# Sheet1.net
KiCad netlist of a schematic drawn in Altium Designer
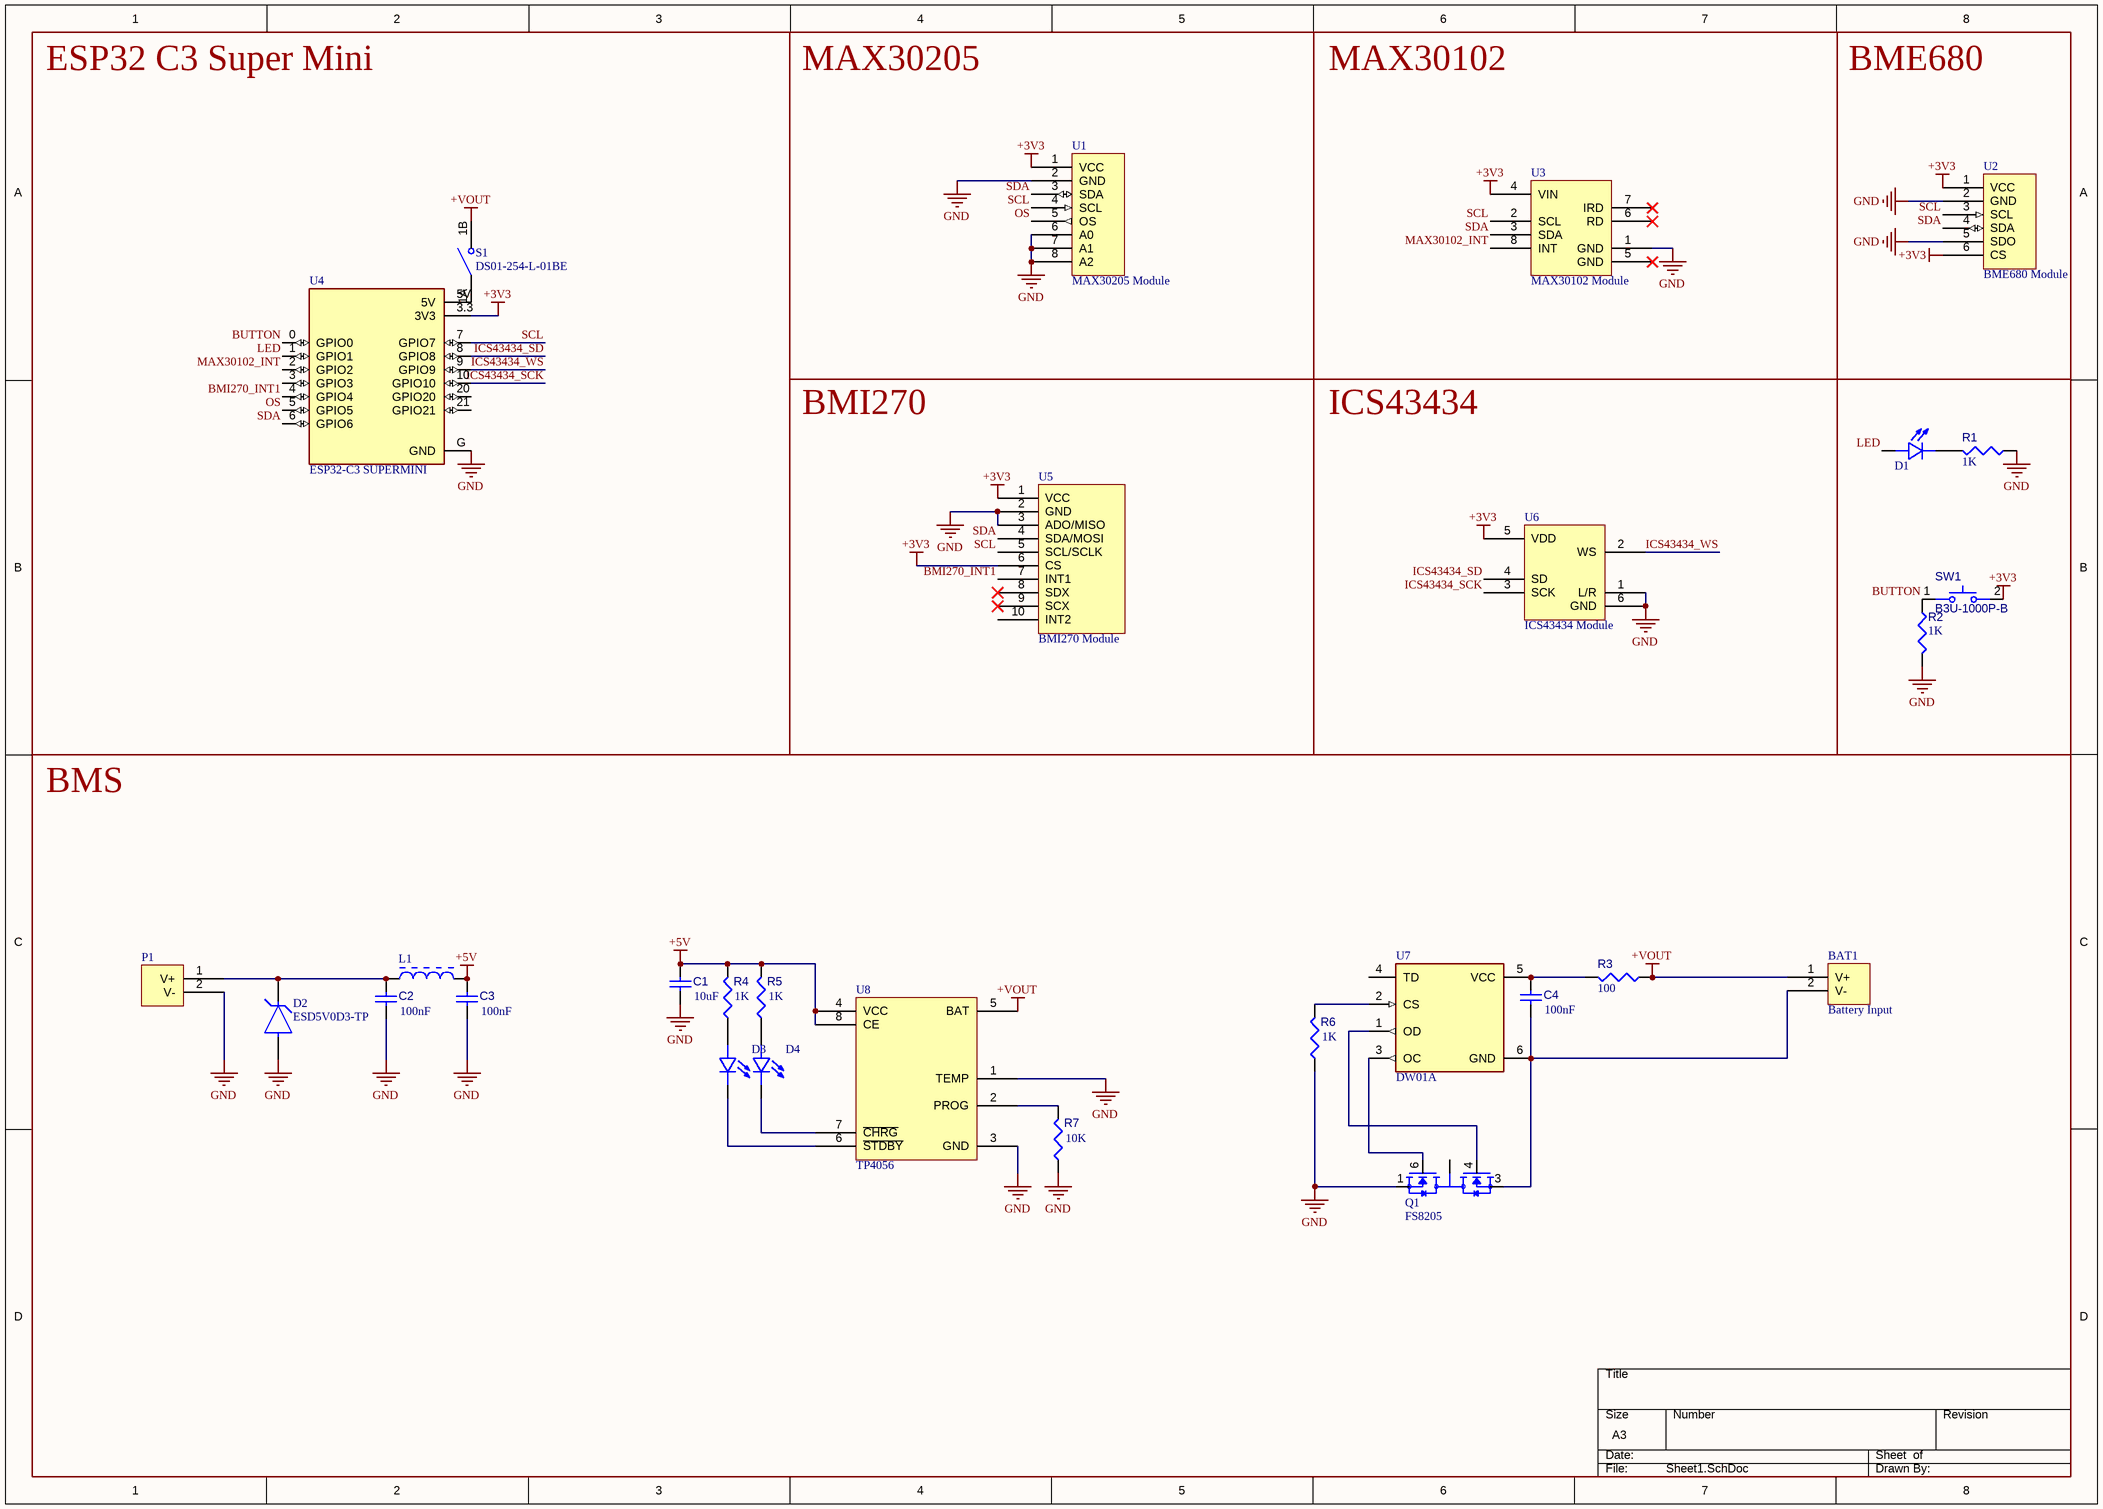
[diagram p0: Sheet1.SchDoc]

(export (version "E")
  (design (tool "Eeschema 10.0.6"))
  (components
    (comp (ref "BAT1")
      (value "Battery Input")
      (footprint "Battery Input-Footprint-1")
      (libsource (lib "personal workspace") (part "Battery Input-Symbol-1"))
    )
    (comp (ref "C1")
      (value "10uF")
      (footprint "Capacitor 0603-Footprint-1")
      (description "Capacitor 0603")
      (libsource (lib "personal workspace") (part "CAP-NP-2"))
    )
    (comp (ref "C2")
      (value "100nF")
      (footprint "Capacitor 0603-Footprint-1")
      (description "Capacitor 0603")
      (libsource (lib "personal workspace") (part "CAP-NP-2"))
    )
    (comp (ref "C3")
      (value "100nF")
      (footprint "Capacitor 0603-Footprint-1")
      (description "Capacitor 0603")
      (libsource (lib "personal workspace") (part "CAP-NP-2"))
    )
    (comp (ref "C4")
      (value "100nF")
      (footprint "Capacitor 0603-Footprint-1")
      (description "Capacitor 0603")
      (libsource (lib "personal workspace") (part "CAP-NP-2"))
    )
    (comp (ref "D1")
      (value "LED 0805")
      (footprint "LEDC2012X120N")
      (description "LED;Red;11mcd;0.061In.Dia.;SMD;100mA;2V Vf;635nm;140deg;SMD;White Diffused;5V Vr")
      (fields
        (field (name "MF") "Lumex Opto/Components")
        (field (name "MP") "SML-LXT0805IW-TR")
        (field (name "SOURCE") "SML-LXT0805IW-TR.SchLib")
      )
      (libsource (lib "") (part "SML-LXT0805IW-TR_1"))
    )
    (comp (ref "D2")
      (value "ESD5V0D3-TP")
      (footprint "FP-SOD-323-IPC_B")
      (description "TVS DIODE 5V 15.5V SOD323")
      (libsource (lib "Altium Content Vault") (part "f813f71cba58e380607f5dd3caf9714"))
    )
    (comp (ref "D3")
      (value "LED 0805")
      (footprint "LEDC2012X120N")
      (description "LED;Red;11mcd;0.061In.Dia.;SMD;100mA;2V Vf;635nm;140deg;SMD;White Diffused;5V Vr")
      (fields
        (field (name "MF") "Lumex Opto/Components")
        (field (name "MP") "SML-LXT0805IW-TR")
        (field (name "SOURCE") "SML-LXT0805IW-TR.SchLib")
      )
      (libsource (lib "personal workspace") (part "SML-LXT0805IW-TR"))
    )
    (comp (ref "D4")
      (value "LED 0805")
      (footprint "LEDC2012X120N")
      (description "LED;Red;11mcd;0.061In.Dia.;SMD;100mA;2V Vf;635nm;140deg;SMD;White Diffused;5V Vr")
      (fields
        (field (name "MF") "Lumex Opto/Components")
        (field (name "MP") "SML-LXT0805IW-TR")
        (field (name "SOURCE") "SML-LXT0805IW-TR.SchLib")
      )
      (libsource (lib "personal workspace") (part "SML-LXT0805IW-TR"))
    )
    (comp (ref "L1")
      (value "Ferrite Bead")
      (footprint "INDC2013X105X50ML20T20")
      (fields (field (name "TOLERANCE") "25%") (field (name "MANUFACTURER") "Murata"))
      (libsource (lib "personal workspace") (part "IND-FB-2"))
    )
    (comp (ref "P1")
      (value "Magnetic Connector 2-Pin 2.54mm")
      (footprint "Magnetic Connector 2-Pin 2.54mm-Footprint-1")
      (libsource (lib "personal workspace") (part "Magnetic Connector 2-Pin 2.54mm-Symbol-1"))
    )
    (comp (ref "Q1")
      (value "FS8205")
      (footprint "SOT95P280X145-6N")
      (description "20V 9A 1.5W Surface Mount SOT-23-6")
      (fields (field (name "MF") "Fortune Semiconductor"))
      (libsource (lib "personal workspace") (part "FS8205"))
    )
    (comp (ref "R1")
      (value "1K")
      (footprint "RESC1608X55X25NL10T15")
      (description "Resistor 0603")
      (libsource (lib "personal workspace") (part "RES-2"))
    )
    (comp (ref "R2")
      (value "1K")
      (footprint "RESC1608X55X25NL10T15")
      (description "Resistor 0603")
      (libsource (lib "personal workspace") (part "RES-2"))
    )
    (comp (ref "R3")
      (value "100")
      (footprint "RESC1608X55X25NL10T15")
      (description "Resistor 0603")
      (libsource (lib "personal workspace") (part "RES-2"))
    )
    (comp (ref "R4")
      (value "1K")
      (footprint "RESC1608X55X25NL10T15")
      (description "Resistor 0603")
      (libsource (lib "personal workspace") (part "RES-2"))
    )
    (comp (ref "R5")
      (value "1K")
      (footprint "RESC1608X55X25NL10T15")
      (description "Resistor 0603")
      (libsource (lib "personal workspace") (part "RES-2"))
    )
    (comp (ref "R6")
      (value "1K")
      (footprint "RESC1608X55X25NL10T15")
      (description "Resistor 0603")
      (libsource (lib "personal workspace") (part "RES-2"))
    )
    (comp (ref "R7")
      (value "10K")
      (footprint "RESC1608X55X25NL10T15")
      (description "Resistor 0603")
      (libsource (lib "personal workspace") (part "RES-2"))
    )
    (comp (ref "S1")
      (value "DS01-254-L-01BE")
      (footprint "SW_DS01-254-L-01BE")
      (description "1 Position, Through Hole, 2.54 mm Pitch, Raised Slide Actuator, Flat Bottom, Long Pin, DIP Switch")
      (fields (field (name "MF") "Same Sky"))
      (libsource (lib "personal workspace") (part "DS01-254-L-01BE"))
    )
    (comp (ref "SW1")
      (value "B3U-1000P-B")
      (footprint "OMRON-B3U-1000P-2-B_V")
      (libsource (lib "personal workspace") (part "CMP-00164-6"))
    )
    (comp (ref "U1")
      (value "MAX30205 Module")
      (footprint "MAX30205 Module-Footprint-1")
      (libsource (lib "personal workspace") (part "MAX30205 Module-Symbol-1"))
    )
    (comp (ref "U2")
      (value "BME680 Module")
      (footprint "BME680 Module-Footprint-1")
      (libsource (lib "personal workspace") (part "BME680 Module-Symbol-1"))
    )
    (comp (ref "U3")
      (value "MAX30102 Module")
      (footprint "MAX30102 Module-Footprint-1")
      (libsource (lib "personal workspace") (part "MAX30102 Module-Symbol-1"))
    )
    (comp (ref "U4")
      (value "ESP32-C3 SUPERMINI")
      (footprint "MODULE_ESP32-C3_SUPERMINI_TH")
      (fields (field (name "MF") "Espressif Systems") (field (name "MP") "ESP32-C3 SuperMini_TH"))
      (libsource (lib "personal workspace") (part "ESP32-C3_SUPERMINI_TH"))
    )
    (comp (ref "U5")
      (value "BMI270 Module")
      (footprint "BMI270 Module-Footprint-1")
      (libsource (lib "personal workspace") (part "BMI270 Module-Symbol-1"))
    )
    (comp (ref "U6")
      (value "ICS43434 Module")
      (footprint "ICS43434 Module-Footprint-1")
      (libsource (lib "personal workspace") (part "ICS43434 Module-Symbol-1"))
    )
    (comp (ref "U7")
      (value "DW01A")
      (footprint "SOT95P280X145-6N")
      (description "One Cell Lithium-ion/Polymer Battery Protection IC")
      (fields (field (name "MF") "Fortune Semiconductor"))
      (libsource (lib "personal workspace") (part "DW01A"))
    )
    (comp (ref "U8")
      (value "TP4056")
      (footprint "SOP127P600X200-8N")
      (description "IC Socket, 16 Contact(s), 2.54mm Term Pitch, 1.014inch Row Spacing, Surface Mount")
      (libsource (lib "personal workspace") (part "TP4056-Symbol-1"))
    )
  )
  (nets
    (net (code "1") (name "+3V3") (class "Default")
      (node (ref "SW1") (pin "2") (pinfunction "2_2") (pintype "passive"))
      (node (ref "U1") (pin "1") (pinfunction "VCC_1") (pintype "power_in"))
      (node (ref "U2") (pin "1") (pinfunction "VCC_1") (pintype "power_in"))
      (node (ref "U2") (pin "6") (pinfunction "CS_6") (pintype "passive"))
      (node (ref "U3") (pin "4") (pinfunction "VIN_4") (pintype "power_in"))
      (node (ref "U4") (pin "3.3") (pinfunction "3V3_3.3") (pintype "power_in"))
      (node (ref "U5") (pin "1") (pinfunction "VCC_1") (pintype "power_in"))
      (node (ref "U5") (pin "6") (pinfunction "CS_6") (pintype "passive"))
      (node (ref "U6") (pin "5") (pinfunction "VDD_5") (pintype "power_in"))
    )
    (net (code "2") (name "+5V") (class "Default")
      (node (ref "C1") (pin "2") (pinfunction "2_2") (pintype "passive"))
      (node (ref "C3") (pin "2") (pinfunction "2_2") (pintype "passive"))
      (node (ref "L1") (pin "2") (pinfunction "2_2") (pintype "passive"))
      (node (ref "R4") (pin "2") (pinfunction "2_2") (pintype "passive"))
      (node (ref "R5") (pin "2") (pinfunction "2_2") (pintype "passive"))
      (node (ref "U8") (pin "4") (pinfunction "VCC_4") (pintype "power_in"))
      (node (ref "U8") (pin "8") (pinfunction "CE_8") (pintype "passive"))
    )
    (net (code "3") (name "+VOUT") (class "Default")
      (node (ref "BAT1") (pin "1") (pinfunction "V+_1") (pintype "power_in"))
      (node (ref "R3") (pin "1") (pinfunction "1_1") (pintype "passive"))
      (node (ref "S1") (pin "1B") (pinfunction "NO1_1B") (pintype "passive"))
      (node (ref "U8") (pin "5") (pinfunction "BAT_5") (pintype "passive"))
    )
    (net (code "4") (name "/BMI270_INT1") (class "Default")
      (node (ref "U4") (pin "4") (pinfunction "GPIO4_4") (pintype "bidirectional"))
      (node (ref "U5") (pin "7") (pinfunction "INT1_7") (pintype "passive"))
    )
    (net (code "5") (name "/BUTTON") (class "Default")
      (node (ref "R2") (pin "1") (pinfunction "1_1") (pintype "passive"))
      (node (ref "SW1") (pin "1") (pinfunction "1_1") (pintype "passive"))
      (node (ref "U4") (pin "0") (pinfunction "GPIO0_0") (pintype "bidirectional"))
    )
    (net (code "6") (name "/ICS43434_SCK") (class "Default")
      (node (ref "U4") (pin "10") (pinfunction "GPIO10_10") (pintype "bidirectional"))
      (node (ref "U6") (pin "3") (pinfunction "SCK_3") (pintype "passive"))
    )
    (net (code "7") (name "/ICS43434_SD") (class "Default")
      (node (ref "U4") (pin "8") (pinfunction "GPIO8_8") (pintype "bidirectional"))
      (node (ref "U6") (pin "4") (pinfunction "SD_4") (pintype "passive"))
    )
    (net (code "8") (name "/ICS43434_WS") (class "Default")
      (node (ref "U4") (pin "9") (pinfunction "GPIO9_9") (pintype "bidirectional"))
      (node (ref "U6") (pin "2") (pinfunction "WS_2") (pintype "passive"))
    )
    (net (code "9") (name "/LED") (class "Default")
      (node (ref "D1") (pin "A") (pinfunction "A_A") (pintype "passive"))
      (node (ref "U4") (pin "1") (pinfunction "GPIO1_1") (pintype "bidirectional"))
    )
    (net (code "10") (name "/MAX30102_INT") (class "Default")
      (node (ref "U3") (pin "8") (pinfunction "INT_8") (pintype "passive"))
      (node (ref "U4") (pin "2") (pinfunction "GPIO2_2") (pintype "bidirectional"))
    )
    (net (code "11") (name "/OS") (class "Default")
      (node (ref "U1") (pin "5") (pinfunction "OS_5") (pintype "output"))
      (node (ref "U4") (pin "5") (pinfunction "GPIO5_5") (pintype "bidirectional"))
    )
    (net (code "12") (name "/SCL") (class "Default")
      (node (ref "U1") (pin "4") (pinfunction "SCL_4") (pintype "input"))
      (node (ref "U2") (pin "3") (pinfunction "SCL_3") (pintype "input"))
      (node (ref "U3") (pin "2") (pinfunction "SCL_2") (pintype "passive"))
      (node (ref "U4") (pin "7") (pinfunction "GPIO7_7") (pintype "bidirectional"))
      (node (ref "U5") (pin "5") (pinfunction "SCL/SCLK_5") (pintype "passive"))
    )
    (net (code "13") (name "/SDA") (class "Default")
      (node (ref "U1") (pin "3") (pinfunction "SDA_3") (pintype "bidirectional"))
      (node (ref "U2") (pin "4") (pinfunction "SDA_4") (pintype "bidirectional"))
      (node (ref "U3") (pin "3") (pinfunction "SDA_3") (pintype "passive"))
      (node (ref "U4") (pin "6") (pinfunction "GPIO6_6") (pintype "bidirectional"))
      (node (ref "U5") (pin "4") (pinfunction "SDA/MOSI_4") (pintype "passive"))
    )
    (net (code "14") (name "GND") (class "Default")
      (node (ref "C1") (pin "1") (pinfunction "1_1") (pintype "passive"))
      (node (ref "C2") (pin "1") (pinfunction "1_1") (pintype "passive"))
      (node (ref "C3") (pin "1") (pinfunction "1_1") (pintype "passive"))
      (node (ref "D2") (pin "2") (pinfunction "A_2") (pintype "passive"))
      (node (ref "P1") (pin "2") (pinfunction "V-_2") (pintype "power_in"))
      (node (ref "Q1") (pin "1") (pinfunction "S1_1") (pintype "passive"))
      (node (ref "R1") (pin "1") (pinfunction "1_1") (pintype "passive"))
      (node (ref "R2") (pin "2") (pinfunction "2_2") (pintype "passive"))
      (node (ref "R6") (pin "1") (pinfunction "1_1") (pintype "passive"))
      (node (ref "R7") (pin "1") (pinfunction "1_1") (pintype "passive"))
      (node (ref "U1") (pin "2") (pinfunction "GND_2") (pintype "power_in"))
      (node (ref "U1") (pin "6") (pinfunction "A0_6") (pintype "passive"))
      (node (ref "U1") (pin "7") (pinfunction "A1_7") (pintype "passive"))
      (node (ref "U1") (pin "8") (pinfunction "A2_8") (pintype "passive"))
      (node (ref "U2") (pin "2") (pinfunction "GND_2") (pintype "power_in"))
      (node (ref "U2") (pin "5") (pinfunction "SDO_5") (pintype "passive"))
      (node (ref "U3") (pin "1") (pinfunction "GND_1") (pintype "power_in"))
      (node (ref "U4") (pin "G") (pinfunction "GND_G") (pintype "power_in"))
      (node (ref "U5") (pin "2") (pinfunction "GND_2") (pintype "power_in"))
      (node (ref "U5") (pin "3") (pinfunction "ADO/MISO_3") (pintype "passive"))
      (node (ref "U6") (pin "1") (pinfunction "L/R_1") (pintype "passive"))
      (node (ref "U6") (pin "6") (pinfunction "GND_6") (pintype "power_in"))
      (node (ref "U8") (pin "1") (pinfunction "TEMP_1") (pintype "passive"))
      (node (ref "U8") (pin "3") (pinfunction "GND_3") (pintype "power_in"))
    )
    (net (code "15") (name "Net-(BAT1-V-)") (class "Default")
      (node (ref "BAT1") (pin "2") (pinfunction "V-_2") (pintype "power_in"))
      (node (ref "C4") (pin "1") (pinfunction "1_1") (pintype "passive"))
      (node (ref "Q1") (pin "3") (pinfunction "S2_3") (pintype "passive"))
      (node (ref "U7") (pin "6") (pinfunction "GND_6") (pintype "power_in"))
    )
    (net (code "16") (name "Net-(D1-PadC)") (class "Default")
      (node (ref "D1") (pin "C") (pinfunction "C_C") (pintype "passive"))
      (node (ref "R1") (pin "2") (pinfunction "2_2") (pintype "passive"))
    )
    (net (code "17") (name "Net-(D2-C)") (class "Default")
      (node (ref "C2") (pin "2") (pinfunction "2_2") (pintype "passive"))
      (node (ref "D2") (pin "1") (pinfunction "C_1") (pintype "passive"))
      (node (ref "L1") (pin "1") (pinfunction "1_1") (pintype "passive"))
      (node (ref "P1") (pin "1") (pinfunction "V+_1") (pintype "power_in"))
    )
    (net (code "18") (name "Net-(D3-PadA)") (class "Default")
      (node (ref "D3") (pin "A") (pinfunction "A_A") (pintype "passive"))
      (node (ref "R4") (pin "1") (pinfunction "1_1") (pintype "passive"))
    )
    (net (code "19") (name "Net-(D4-PadA)") (class "Default")
      (node (ref "D4") (pin "A") (pinfunction "A_A") (pintype "passive"))
      (node (ref "R5") (pin "1") (pinfunction "1_1") (pintype "passive"))
    )
    (net (code "20") (name "Net-(Q1-D12-Pad2)") (class "Default")
      (node (ref "Q1") (pin "2") (pinfunction "D12_2") (pintype "passive"))
      (node (ref "Q1") (pin "5") (pinfunction "D12_5") (pintype "passive"))
    )
    (net (code "21") (name "Net-(Q1-G1)") (class "Default")
      (node (ref "Q1") (pin "6") (pinfunction "G1_6") (pintype "passive"))
      (node (ref "U7") (pin "3") (pinfunction "OC_3") (pintype "output"))
    )
    (net (code "22") (name "Net-(Q1-G2)") (class "Default")
      (node (ref "Q1") (pin "4") (pinfunction "G2_4") (pintype "passive"))
      (node (ref "U7") (pin "1") (pinfunction "OD_1") (pintype "output"))
    )
    (net (code "23") (name "Net-(S1-COM1)") (class "Default")
      (node (ref "S1") (pin "1A") (pinfunction "COM1_1A") (pintype "passive"))
      (node (ref "U4") (pin "5V") (pinfunction "5V_5V") (pintype "power_in"))
    )
    (net (code "24") (name "Net-(U7-CS)") (class "Default")
      (node (ref "R6") (pin "2") (pinfunction "2_2") (pintype "passive"))
      (node (ref "U7") (pin "2") (pinfunction "CS_2") (pintype "input"))
    )
    (net (code "25") (name "Net-(U7-VCC)") (class "Default")
      (node (ref "C4") (pin "2") (pinfunction "2_2") (pintype "passive"))
      (node (ref "R3") (pin "2") (pinfunction "2_2") (pintype "passive"))
      (node (ref "U7") (pin "5") (pinfunction "VCC_5") (pintype "power_in"))
    )
    (net (code "26") (name "Net-(U8-PROG)") (class "Default")
      (node (ref "R7") (pin "2") (pinfunction "2_2") (pintype "passive"))
      (node (ref "U8") (pin "2") (pinfunction "PROG_2") (pintype "passive"))
    )
    (net (code "27") (name "Net-(U8-~{CHRG})") (class "Default")
      (node (ref "D4") (pin "C") (pinfunction "C_C") (pintype "passive"))
      (node (ref "U8") (pin "7") (pinfunction "~{CHRG}_7") (pintype "passive"))
    )
    (net (code "28") (name "Net-(U8-~{STDBY})") (class "Default")
      (node (ref "D3") (pin "C") (pinfunction "C_C") (pintype "passive"))
      (node (ref "U8") (pin "6") (pinfunction "~{STDBY}_6") (pintype "passive"))
    )
    (net (code "29") (name "unconnected-(U3-GND-Pad5)") (class "Default")
      (node (ref "U3") (pin "5") (pinfunction "GND_5") (pintype "power_in+no_connect"))
    )
    (net (code "30") (name "unconnected-(U3-IRD-Pad7)") (class "Default")
      (node (ref "U3") (pin "7") (pinfunction "IRD_7") (pintype "passive+no_connect"))
    )
    (net (code "31") (name "unconnected-(U3-RD-Pad6)") (class "Default")
      (node (ref "U3") (pin "6") (pinfunction "RD_6") (pintype "passive+no_connect"))
    )
    (net (code "32") (name "unconnected-(U4-GPIO3-Pad3)") (class "Default")
      (node (ref "U4") (pin "3") (pinfunction "GPIO3_3") (pintype "bidirectional"))
    )
    (net (code "33") (name "unconnected-(U4-GPIO20-Pad20)") (class "Default")
      (node (ref "U4") (pin "20") (pinfunction "GPIO20_20") (pintype "bidirectional"))
    )
    (net (code "34") (name "unconnected-(U4-GPIO21-Pad21)") (class "Default")
      (node (ref "U4") (pin "21") (pinfunction "GPIO21_21") (pintype "bidirectional"))
    )
    (net (code "35") (name "unconnected-(U5-INT2-Pad10)") (class "Default")
      (node (ref "U5") (pin "10") (pinfunction "INT2_10") (pintype "passive"))
    )
    (net (code "36") (name "unconnected-(U5-SCX-Pad9)") (class "Default")
      (node (ref "U5") (pin "9") (pinfunction "SCX_9") (pintype "passive+no_connect"))
    )
    (net (code "37") (name "unconnected-(U5-SDX-Pad8)") (class "Default")
      (node (ref "U5") (pin "8") (pinfunction "SDX_8") (pintype "passive+no_connect"))
    )
    (net (code "38") (name "unconnected-(U7-TD-Pad4)") (class "Default")
      (node (ref "U7") (pin "4") (pinfunction "TD_4") (pintype "passive"))
    )
  )
)
